# Joystick.net
KiCad netlist of a schematic drawn in Altium Designer
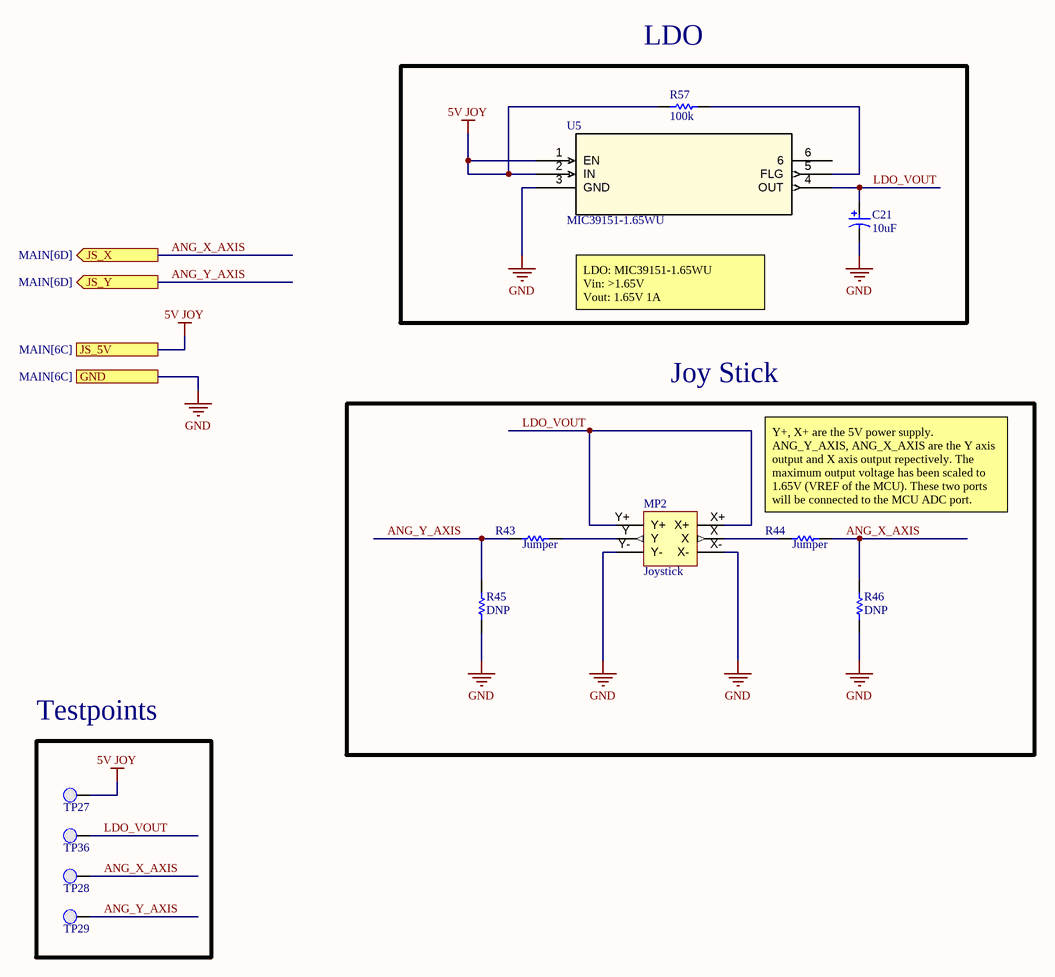
[diagram p0: Joystick.SchDoc]

(export (version "E")
  (design (tool "Eeschema 10.0.6"))
  (components
    (comp (ref "C21")
      (value "10uF")
      (footprint "TMCHC1C106MTRF")
      (description "10uF TMCHC1C106MTRF LDO capacitor")
      (fields (field (name "MANUFACTURER PART NUMBER") "TMCHC1C106MTRF"))
      (libsource (lib "Schlib1") (part "TMCHC1C106MTRF"))
    )
    (comp (ref "MP2") (value "Joystick") (footprint "Joystick") (libsource (lib "Schlib1") (part "Joystick")))
    (comp (ref "R43")
      (value "Jumper")
      (footprint "RESC0603(1608)_N")
      (description "Jumper 0603 (1608 Metric)")
      (fields (field (name "POWER") "None"))
      (libsource (lib "Altium Content Vault") (part "RES"))
    )
    (comp (ref "R44")
      (value "Jumper")
      (footprint "RESC0603(1608)_N")
      (description "Jumper 0603 (1608 Metric)")
      (fields (field (name "POWER") "None"))
      (libsource (lib "Altium Content Vault") (part "RES"))
    )
    (comp (ref "R45") (value "DNP") (footprint "DNP") (libsource (lib "Schlib1") (part "DNP")))
    (comp (ref "R46") (value "DNP") (footprint "DNP") (libsource (lib "Schlib1") (part "DNP")))
    (comp (ref "R57")
      (value "100k")
      (footprint "RESC1609X55X30ML10T20")
      (fields (field (name "MANUFACTURER") "Vishay Dale") (field (name "PART NUMBER") "TNPW0603100KBEEA"))
      (libsource (lib "Altium Content Vault") (part "RES"))
    )
    (comp (ref "TP27")
      (value "0.1\" Pad")
      (footprint "PCBComponent")
      (libsource (lib "Components - 12.02.20 - 18.05") (part "0.1{dblquote} Pad-A.4"))
    )
    (comp (ref "TP28")
      (value "0.1\" Pad")
      (footprint "PCBComponent")
      (libsource (lib "Components - 12.02.20 - 18.05") (part "0.1{dblquote} Pad-A.4"))
    )
    (comp (ref "TP29")
      (value "0.1\" Pad")
      (footprint "PCBComponent")
      (libsource (lib "Components - 12.02.20 - 18.05") (part "0.1{dblquote} Pad-A.4"))
    )
    (comp (ref "TP36")
      (value "0.1\" Pad")
      (footprint "PCBComponent")
      (libsource (lib "Components - 12.02.20 - 18.05") (part "0.1{dblquote} Pad-A.4"))
    )
    (comp (ref "U5")
      (value "MIC39151-1.65WU")
      (footprint "TO-263-5_MCL")
      (description "No Description Available")
      (fields (field (name "COPYRIGHT") "Copyright (C) 2022 Ultra Librarian. All rights reserved."))
      (libsource (lib "MIC39151-1P65WU") (part "MIC39151-1.65WU"))
    )
  )
  (nets
    (net (code "1") (name "/ANG_X_AXIS") (class "Default")
      (node (ref "R44") (pin "2") (pinfunction "2_2") (pintype "passive"))
      (node (ref "R46") (pin "2") (pinfunction "2_2") (pintype "passive"))
      (node (ref "TP28") (pin "1") (pinfunction "PAD_1") (pintype "passive"))
    )
    (net (code "2") (name "/ANG_Y_AXIS") (class "Default")
      (node (ref "R43") (pin "1") (pinfunction "1_1") (pintype "passive"))
      (node (ref "R45") (pin "2") (pinfunction "2_2") (pintype "passive"))
      (node (ref "TP29") (pin "1") (pinfunction "PAD_1") (pintype "passive"))
    )
    (net (code "3") (name "/LDO_VOUT") (class "Default")
      (node (ref "C21") (pin "1") (pinfunction "1_1") (pintype "passive"))
      (node (ref "MP2") (pin "X+") (pinfunction "X+_X+") (pintype "passive"))
      (node (ref "MP2") (pin "Y+") (pinfunction "Y+_Y+") (pintype "passive"))
      (node (ref "TP36") (pin "1") (pinfunction "PAD_1") (pintype "passive"))
      (node (ref "U5") (pin "4") (pinfunction "OUT_4") (pintype "output"))
    )
    (net (code "4") (name "5V JOY") (class "Default")
      (node (ref "R57") (pin "1") (pinfunction "1_1") (pintype "passive"))
      (node (ref "TP27") (pin "1") (pinfunction "PAD_1") (pintype "passive"))
      (node (ref "U5") (pin "1") (pinfunction "EN_1") (pintype "input"))
      (node (ref "U5") (pin "2") (pinfunction "IN_2") (pintype "input"))
    )
    (net (code "5") (name "GND") (class "Default")
      (node (ref "C21") (pin "2") (pinfunction "2_2") (pintype "passive"))
      (node (ref "MP2") (pin "X-") (pinfunction "X-_X-") (pintype "power_in"))
      (node (ref "MP2") (pin "Y-") (pinfunction "Y-_Y-") (pintype "power_in"))
      (node (ref "R45") (pin "1") (pinfunction "1_1") (pintype "passive"))
      (node (ref "R46") (pin "1") (pinfunction "1_1") (pintype "passive"))
      (node (ref "U5") (pin "3") (pinfunction "GND_3") (pintype "power_in"))
    )
    (net (code "6") (name "Net-(MP2-PadX)") (class "Default")
      (node (ref "MP2") (pin "X") (pinfunction "X_X") (pintype "output"))
      (node (ref "R44") (pin "1") (pinfunction "1_1") (pintype "passive"))
    )
    (net (code "7") (name "Net-(MP2-PadY)") (class "Default")
      (node (ref "MP2") (pin "Y") (pinfunction "Y_Y") (pintype "output"))
      (node (ref "R43") (pin "2") (pinfunction "2_2") (pintype "passive"))
    )
    (net (code "8") (name "Net-(U5-FLG)") (class "Default")
      (node (ref "R57") (pin "2") (pinfunction "2_2") (pintype "passive"))
      (node (ref "U5") (pin "5") (pinfunction "FLG_5") (pintype "output"))
    )
    (net (code "9") (name "unconnected-(U5-Pad6)") (class "Default")
      (node (ref "U5") (pin "6") (pinfunction "6_6") (pintype "passive"))
    )
  )
)
